# v001.net
KiCad netlist of a schematic drawn in EAGLE
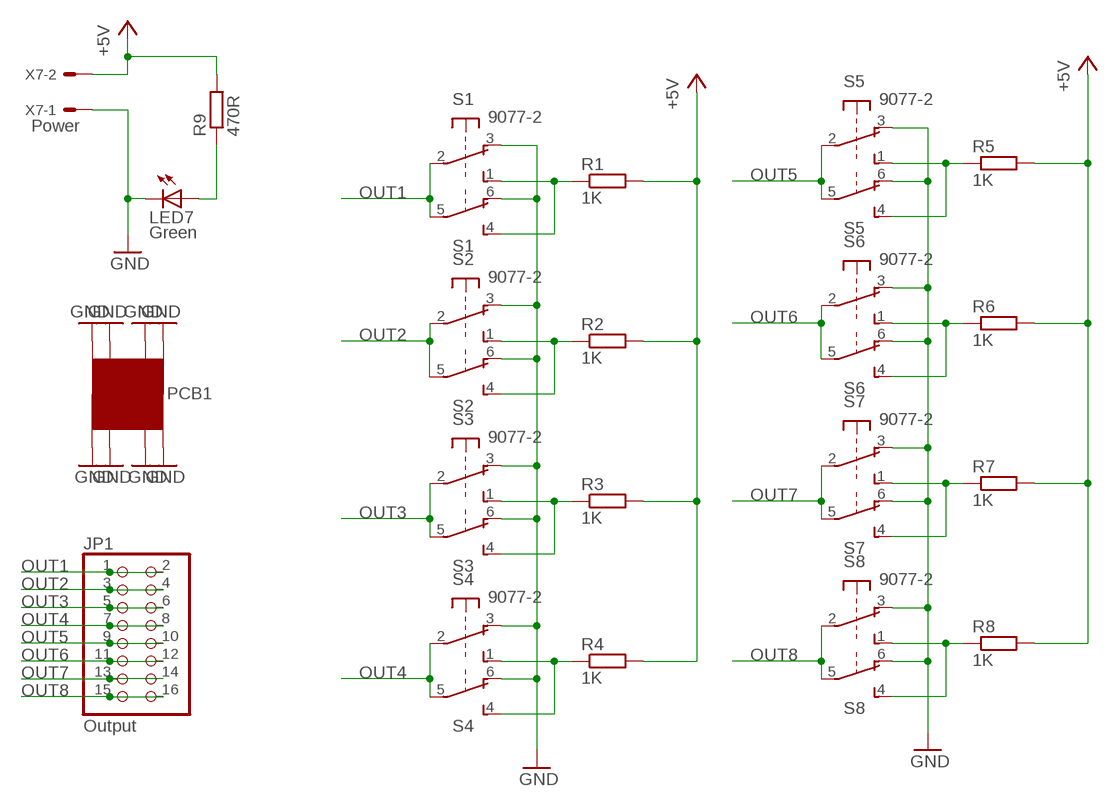
[diagram p0: schematic, sheet 1]

(export (version "E")
  (design (tool "Eeschema 10.0.6"))
  (components
    (comp (ref "JP1")
      (value "Output")
      (footprint "eagle-import:2X08")
      (libsource (lib "eagle-import") (part "PINHD-2X8"))
    )
    (comp (ref "LED7")
      (value "Green")
      (footprint "eagle-import:LED3MM")
      (libsource (lib "eagle-import") (part "LED3MM"))
    )
    (comp (ref "PCB1")
      (value "PCB05X05")
      (footprint "eagle-import:PCB_05X05")
      (libsource (lib "eagle-import") (part "PCB05X05"))
    )
    (comp (ref "R1")
      (value "1K")
      (footprint "eagle-import:0207_2V")
      (libsource (lib "eagle-import") (part "R-EU_0207/2V"))
    )
    (comp (ref "R2")
      (value "1K")
      (footprint "eagle-import:0207_2V")
      (libsource (lib "eagle-import") (part "R-EU_0207/2V"))
    )
    (comp (ref "R3")
      (value "1K")
      (footprint "eagle-import:0207_2V")
      (libsource (lib "eagle-import") (part "R-EU_0207/2V"))
    )
    (comp (ref "R4")
      (value "1K")
      (footprint "eagle-import:0207_2V")
      (libsource (lib "eagle-import") (part "R-EU_0207/2V"))
    )
    (comp (ref "R5")
      (value "1K")
      (footprint "eagle-import:0207_2V")
      (libsource (lib "eagle-import") (part "R-EU_0207/2V"))
    )
    (comp (ref "R6")
      (value "1K")
      (footprint "eagle-import:0207_2V")
      (libsource (lib "eagle-import") (part "R-EU_0207/2V"))
    )
    (comp (ref "R7")
      (value "1K")
      (footprint "eagle-import:0207_2V")
      (libsource (lib "eagle-import") (part "R-EU_0207/2V"))
    )
    (comp (ref "R8")
      (value "1K")
      (footprint "eagle-import:0207_2V")
      (libsource (lib "eagle-import") (part "R-EU_0207/2V"))
    )
    (comp (ref "R9")
      (value "470R")
      (footprint "eagle-import:0207_2V")
      (libsource (lib "eagle-import") (part "resistor_R-EU_0207/2V"))
    )
    (comp (ref "S1")
      (value "9077-2")
      (footprint "eagle-import:9077-2")
      (libsource (lib "eagle-import") (part "9077-2"))
    )
    (comp (ref "S2")
      (value "9077-2")
      (footprint "eagle-import:9077-2")
      (libsource (lib "eagle-import") (part "9077-2"))
    )
    (comp (ref "S3")
      (value "9077-2")
      (footprint "eagle-import:9077-2")
      (libsource (lib "eagle-import") (part "9077-2"))
    )
    (comp (ref "S4")
      (value "9077-2")
      (footprint "eagle-import:9077-2")
      (libsource (lib "eagle-import") (part "9077-2"))
    )
    (comp (ref "S5")
      (value "9077-2")
      (footprint "eagle-import:9077-2")
      (libsource (lib "eagle-import") (part "9077-2"))
    )
    (comp (ref "S6")
      (value "9077-2")
      (footprint "eagle-import:9077-2")
      (libsource (lib "eagle-import") (part "9077-2"))
    )
    (comp (ref "S7")
      (value "9077-2")
      (footprint "eagle-import:9077-2")
      (libsource (lib "eagle-import") (part "9077-2"))
    )
    (comp (ref "S8")
      (value "9077-2")
      (footprint "eagle-import:9077-2")
      (libsource (lib "eagle-import") (part "9077-2"))
    )
    (comp (ref "X7")
      (value "Power")
      (footprint "eagle-import:6410-02")
      (libsource (lib "eagle-import") (part "22-?-0227-2021"))
    )
  )
  (nets
    (net (code "1") (name "+5V") (class "Default")
      (node (ref "R1") (pin "2") (pinfunction "2_2") (pintype "passive"))
      (node (ref "R2") (pin "2") (pinfunction "2_2") (pintype "passive"))
      (node (ref "R3") (pin "2") (pinfunction "2_2") (pintype "passive"))
      (node (ref "R4") (pin "2") (pinfunction "2_2") (pintype "passive"))
      (node (ref "R5") (pin "2") (pinfunction "2_2") (pintype "passive"))
      (node (ref "R6") (pin "2") (pinfunction "2_2") (pintype "passive"))
      (node (ref "R7") (pin "2") (pinfunction "2_2") (pintype "passive"))
      (node (ref "R8") (pin "2") (pinfunction "2_2") (pintype "passive"))
      (node (ref "R9") (pin "2") (pinfunction "2_2") (pintype "passive"))
      (node (ref "X7") (pin "2") (pinfunction "S_2") (pintype "passive"))
    )
    (net (code "2") (name "/OUT1") (class "Default")
      (node (ref "JP1") (pin "1") (pinfunction "1_1") (pintype "passive"))
      (node (ref "JP1") (pin "2") (pinfunction "2_2") (pintype "passive"))
      (node (ref "S1") (pin "2") (pinfunction "P_2") (pintype "passive"))
      (node (ref "S1") (pin "5") (pinfunction "P_5") (pintype "passive"))
    )
    (net (code "3") (name "/OUT2") (class "Default")
      (node (ref "JP1") (pin "3") (pinfunction "3_3") (pintype "passive"))
      (node (ref "JP1") (pin "4") (pinfunction "4_4") (pintype "passive"))
      (node (ref "S2") (pin "2") (pinfunction "P_2") (pintype "passive"))
      (node (ref "S2") (pin "5") (pinfunction "P_5") (pintype "passive"))
    )
    (net (code "4") (name "/OUT3") (class "Default")
      (node (ref "JP1") (pin "5") (pinfunction "5_5") (pintype "passive"))
      (node (ref "JP1") (pin "6") (pinfunction "6_6") (pintype "passive"))
      (node (ref "S3") (pin "2") (pinfunction "P_2") (pintype "passive"))
      (node (ref "S3") (pin "5") (pinfunction "P_5") (pintype "passive"))
    )
    (net (code "5") (name "/OUT4") (class "Default")
      (node (ref "JP1") (pin "7") (pinfunction "7_7") (pintype "passive"))
      (node (ref "JP1") (pin "8") (pinfunction "8_8") (pintype "passive"))
      (node (ref "S4") (pin "2") (pinfunction "P_2") (pintype "passive"))
      (node (ref "S4") (pin "5") (pinfunction "P_5") (pintype "passive"))
    )
    (net (code "6") (name "/OUT5") (class "Default")
      (node (ref "JP1") (pin "10") (pinfunction "10_10") (pintype "passive"))
      (node (ref "JP1") (pin "9") (pinfunction "9_9") (pintype "passive"))
      (node (ref "S5") (pin "2") (pinfunction "P_2") (pintype "passive"))
      (node (ref "S5") (pin "5") (pinfunction "P_5") (pintype "passive"))
    )
    (net (code "7") (name "/OUT6") (class "Default")
      (node (ref "JP1") (pin "11") (pinfunction "11_11") (pintype "passive"))
      (node (ref "JP1") (pin "12") (pinfunction "12_12") (pintype "passive"))
      (node (ref "S6") (pin "2") (pinfunction "P_2") (pintype "passive"))
      (node (ref "S6") (pin "5") (pinfunction "P_5") (pintype "passive"))
    )
    (net (code "8") (name "/OUT7") (class "Default")
      (node (ref "JP1") (pin "13") (pinfunction "13_13") (pintype "passive"))
      (node (ref "JP1") (pin "14") (pinfunction "14_14") (pintype "passive"))
      (node (ref "S7") (pin "2") (pinfunction "P_2") (pintype "passive"))
      (node (ref "S7") (pin "5") (pinfunction "P_5") (pintype "passive"))
    )
    (net (code "9") (name "/OUT8") (class "Default")
      (node (ref "JP1") (pin "15") (pinfunction "15_15") (pintype "passive"))
      (node (ref "JP1") (pin "16") (pinfunction "16_16") (pintype "passive"))
      (node (ref "S8") (pin "2") (pinfunction "P_2") (pintype "passive"))
      (node (ref "S8") (pin "5") (pinfunction "P_5") (pintype "passive"))
    )
    (net (code "10") (name "GND") (class "Default")
      (node (ref "LED7") (pin "K") (pinfunction "C_K") (pintype "passive"))
      (node (ref "PCB1") (pin "GND@1") (pinfunction "GND_GND@1") (pintype "bidirectional"))
      (node (ref "PCB1") (pin "GND@2") (pinfunction "GND_GND@2") (pintype "bidirectional"))
      (node (ref "PCB1") (pin "GND@3") (pinfunction "GND_GND@3") (pintype "bidirectional"))
      (node (ref "PCB1") (pin "GND@4") (pinfunction "GND_GND@4") (pintype "bidirectional"))
      (node (ref "PCB1") (pin "GND@5") (pinfunction "GND_GND@5") (pintype "bidirectional"))
      (node (ref "PCB1") (pin "GND@6") (pinfunction "GND_GND@6") (pintype "bidirectional"))
      (node (ref "PCB1") (pin "GND@7") (pinfunction "GND_GND@7") (pintype "bidirectional"))
      (node (ref "PCB1") (pin "GND@8") (pinfunction "GND_GND@8") (pintype "bidirectional"))
      (node (ref "S1") (pin "3") (pinfunction "O_3") (pintype "passive"))
      (node (ref "S1") (pin "6") (pinfunction "O_6") (pintype "passive"))
      (node (ref "S2") (pin "3") (pinfunction "O_3") (pintype "passive"))
      (node (ref "S2") (pin "6") (pinfunction "O_6") (pintype "passive"))
      (node (ref "S3") (pin "3") (pinfunction "O_3") (pintype "passive"))
      (node (ref "S3") (pin "6") (pinfunction "O_6") (pintype "passive"))
      (node (ref "S4") (pin "3") (pinfunction "O_3") (pintype "passive"))
      (node (ref "S4") (pin "6") (pinfunction "O_6") (pintype "passive"))
      (node (ref "S5") (pin "3") (pinfunction "O_3") (pintype "passive"))
      (node (ref "S5") (pin "6") (pinfunction "O_6") (pintype "passive"))
      (node (ref "S6") (pin "3") (pinfunction "O_3") (pintype "passive"))
      (node (ref "S6") (pin "6") (pinfunction "O_6") (pintype "passive"))
      (node (ref "S7") (pin "3") (pinfunction "O_3") (pintype "passive"))
      (node (ref "S7") (pin "6") (pinfunction "O_6") (pintype "passive"))
      (node (ref "S8") (pin "3") (pinfunction "O_3") (pintype "passive"))
      (node (ref "S8") (pin "6") (pinfunction "O_6") (pintype "passive"))
      (node (ref "X7") (pin "1") (pinfunction "S_1") (pintype "passive"))
    )
    (net (code "11") (name "Net-(LED7-PadA)") (class "Default")
      (node (ref "LED7") (pin "A") (pinfunction "A_A") (pintype "passive"))
      (node (ref "R9") (pin "1") (pinfunction "1_1") (pintype "passive"))
    )
    (net (code "12") (name "Net-(S1A-S)") (class "Default")
      (node (ref "R1") (pin "1") (pinfunction "1_1") (pintype "passive"))
      (node (ref "S1") (pin "1") (pinfunction "S_1") (pintype "passive"))
      (node (ref "S1") (pin "4") (pinfunction "S_4") (pintype "passive"))
    )
    (net (code "13") (name "Net-(S2A-S)") (class "Default")
      (node (ref "R2") (pin "1") (pinfunction "1_1") (pintype "passive"))
      (node (ref "S2") (pin "1") (pinfunction "S_1") (pintype "passive"))
      (node (ref "S2") (pin "4") (pinfunction "S_4") (pintype "passive"))
    )
    (net (code "14") (name "Net-(S3A-S)") (class "Default")
      (node (ref "R3") (pin "1") (pinfunction "1_1") (pintype "passive"))
      (node (ref "S3") (pin "1") (pinfunction "S_1") (pintype "passive"))
      (node (ref "S3") (pin "4") (pinfunction "S_4") (pintype "passive"))
    )
    (net (code "15") (name "Net-(S4A-S)") (class "Default")
      (node (ref "R4") (pin "1") (pinfunction "1_1") (pintype "passive"))
      (node (ref "S4") (pin "1") (pinfunction "S_1") (pintype "passive"))
      (node (ref "S4") (pin "4") (pinfunction "S_4") (pintype "passive"))
    )
    (net (code "16") (name "Net-(S5A-S)") (class "Default")
      (node (ref "R5") (pin "1") (pinfunction "1_1") (pintype "passive"))
      (node (ref "S5") (pin "1") (pinfunction "S_1") (pintype "passive"))
      (node (ref "S5") (pin "4") (pinfunction "S_4") (pintype "passive"))
    )
    (net (code "17") (name "Net-(S6A-S)") (class "Default")
      (node (ref "R6") (pin "1") (pinfunction "1_1") (pintype "passive"))
      (node (ref "S6") (pin "1") (pinfunction "S_1") (pintype "passive"))
      (node (ref "S6") (pin "4") (pinfunction "S_4") (pintype "passive"))
    )
    (net (code "18") (name "Net-(S7A-S)") (class "Default")
      (node (ref "R7") (pin "1") (pinfunction "1_1") (pintype "passive"))
      (node (ref "S7") (pin "1") (pinfunction "S_1") (pintype "passive"))
      (node (ref "S7") (pin "4") (pinfunction "S_4") (pintype "passive"))
    )
    (net (code "19") (name "Net-(S8A-S)") (class "Default")
      (node (ref "R8") (pin "1") (pinfunction "1_1") (pintype "passive"))
      (node (ref "S8") (pin "1") (pinfunction "S_1") (pintype "passive"))
      (node (ref "S8") (pin "4") (pinfunction "S_4") (pintype "passive"))
    )
  )
)
